# Sheet1.net
KiCad netlist of a schematic drawn in Altium Designer
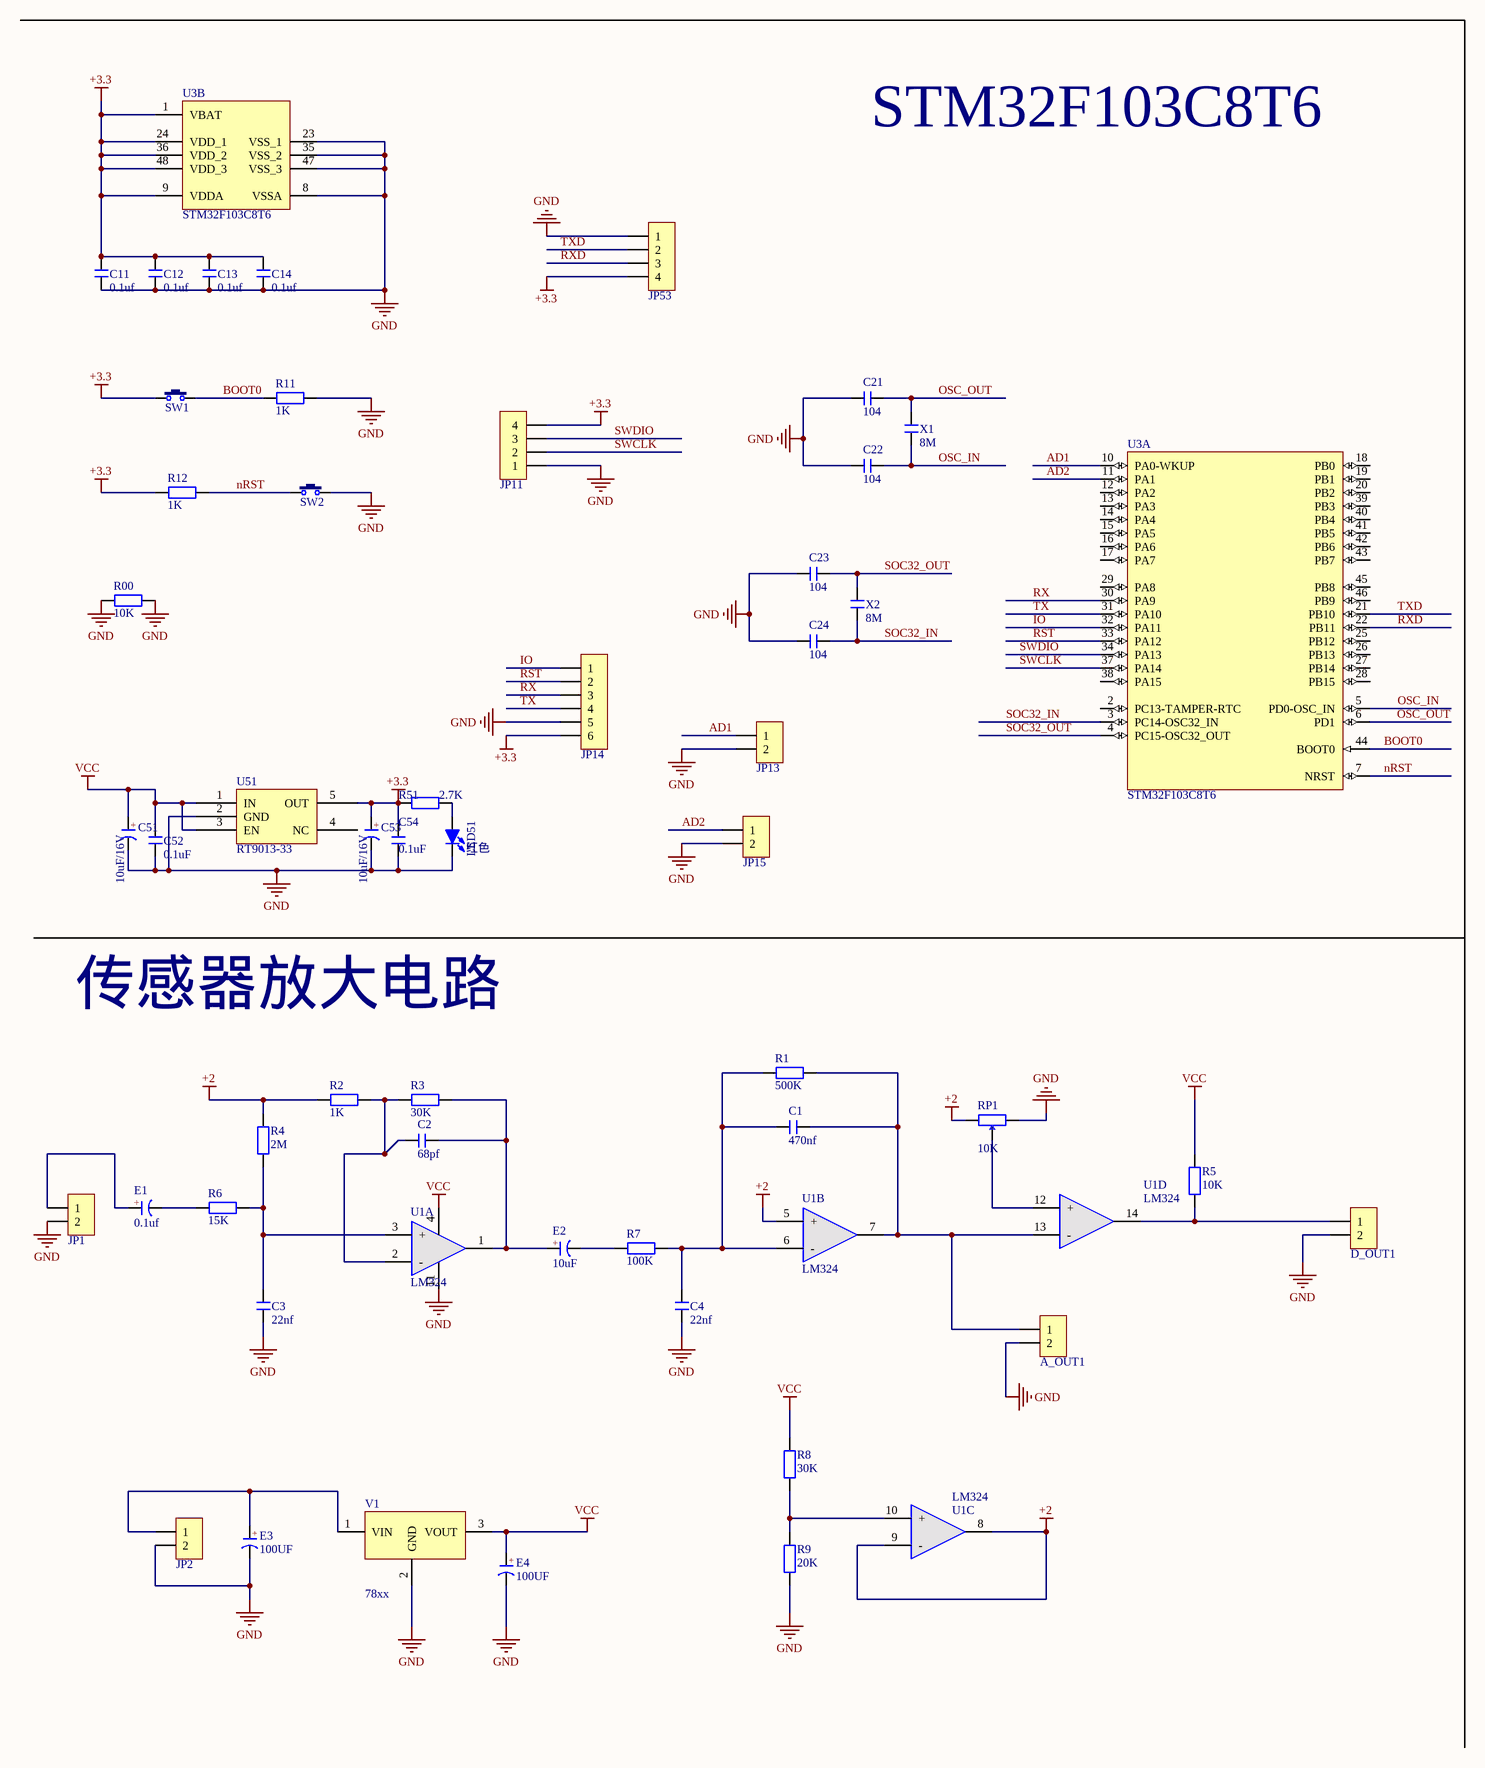
[diagram p0: Sheet1.SchDoc]

(export (version "E")
  (design (tool "Eeschema 10.0.6"))
  (components
    (comp (ref "A_OUT1")
      (value "HDR-1X2")
      (footprint "XH2.54-WI-2P")
      (description "2P接插件")
      (fields (field (name "版权归属") "封装库来自淘宝 ID：黄晶宝石"))
      (libsource (lib "5.3 - 接插件-脚距2.54 (100mil) ") (part "Header 2"))
    )
    (comp (ref "C1")
      (value "470nf")
      (footprint "C 0805_L")
      (description "贴片电容")
      (libsource (lib "0.1 - 电阻-电容-电感") (part "C"))
    )
    (comp (ref "C2")
      (value "68pf")
      (footprint "C 0805_L")
      (description "贴片电容")
      (libsource (lib "0.1 - 电阻-电容-电感") (part "C"))
    )
    (comp (ref "C3")
      (value "22nf")
      (footprint "C 0805_L")
      (description "贴片电容")
      (libsource (lib "0.1 - 电阻-电容-电感") (part "C"))
    )
    (comp (ref "C4")
      (value "22nf")
      (footprint "C 0805_L")
      (description "贴片电容")
      (libsource (lib "0.1 - 电阻-电容-电感") (part "C"))
    )
    (comp (ref "C11")
      (value "0.1uf")
      (footprint "C 0805_L")
      (description "贴片电容")
      (libsource (lib "0.1 - 电阻-电容-电感") (part "C"))
    )
    (comp (ref "C12")
      (value "0.1uf")
      (footprint "C 0805_L")
      (description "贴片电容")
      (libsource (lib "0.1 - 电阻-电容-电感") (part "C"))
    )
    (comp (ref "C13")
      (value "0.1uf")
      (footprint "C 0805_L")
      (description "贴片电容")
      (libsource (lib "0.1 - 电阻-电容-电感") (part "C"))
    )
    (comp (ref "C14")
      (value "0.1uf")
      (footprint "C 0805_L")
      (description "贴片电容")
      (libsource (lib "0.1 - 电阻-电容-电感") (part "C"))
    )
    (comp (ref "C21")
      (value "104")
      (footprint "C 0805_L")
      (description "贴片电容")
      (libsource (lib "0.1 - 电阻-电容-电感") (part "C"))
    )
    (comp (ref "C22")
      (value "104")
      (footprint "C 0805_L")
      (description "贴片电容")
      (libsource (lib "0.1 - 电阻-电容-电感") (part "C"))
    )
    (comp (ref "C23")
      (value "104")
      (footprint "C 0805_L")
      (description "贴片电容")
      (libsource (lib "0.1 - 电阻-电容-电感") (part "C"))
    )
    (comp (ref "C24")
      (value "104")
      (footprint "C 0805_L")
      (description "贴片电容")
      (libsource (lib "0.1 - 电阻-电容-电感") (part "C"))
    )
    (comp (ref "C51")
      (value "10uF/16V")
      (footprint "CD A(3216)")
      (description "贴片钽电容")
      (libsource (lib "TC264") (part "CT"))
    )
    (comp (ref "C52")
      (value "0.1uF")
      (footprint "C 0805_L")
      (description "贴片电容")
      (libsource (lib "TC264") (part "C"))
    )
    (comp (ref "C53")
      (value "10uF/16V")
      (footprint "CD A(3216)")
      (description "贴片钽电容")
      (libsource (lib "TC264") (part "CT"))
    )
    (comp (ref "C54")
      (value "0.1uF")
      (footprint "C 0805_L")
      (description "贴片电容")
      (libsource (lib "TC264") (part "C"))
    )
    (comp (ref "D_OUT1")
      (value "HDR-1X2")
      (footprint "XH2.54-WI-2P")
      (description "2P接插件")
      (fields (field (name "版权归属") "封装库来自淘宝 ID：黄晶宝石"))
      (libsource (lib "5.3 - 接插件-脚距2.54 (100mil) ") (part "Header 2"))
    )
    (comp (ref "E1")
      (value "0.1uf")
      (footprint "CM B(4*5.4)")
      (description "贴片电解电容")
      (fields (field (name "版权归属") "封装库来自淘宝 ID：黄晶宝石"))
      (libsource (lib "") (part "CE_SMD_1"))
    )
    (comp (ref "E2")
      (value "10uF")
      (footprint "CM B(4*5.4)")
      (description "贴片电解电容")
      (fields (field (name "版权归属") "封装库来自淘宝 ID：黄晶宝石"))
      (libsource (lib "") (part "CE_SMD_1"))
    )
    (comp (ref "E3")
      (value "100UF")
      (footprint "CM B(4*5.4)")
      (description "贴片电解电容")
      (fields (field (name "版权归属") "封装库来自淘宝 ID：黄晶宝石"))
      (libsource (lib "0.1 - 电阻-电容-电感") (part "CE_SMD"))
    )
    (comp (ref "E4")
      (value "100UF")
      (footprint "CM B(4*5.4)")
      (description "贴片电解电容")
      (fields (field (name "版权归属") "封装库来自淘宝 ID：黄晶宝石"))
      (libsource (lib "0.1 - 电阻-电容-电感") (part "CE_SMD"))
    )
    (comp (ref "JP1")
      (value "HDR-1X2")
      (footprint "XH2.54-WI-2P")
      (description "2P接插件")
      (fields (field (name "版权归属") "封装库来自淘宝 ID：黄晶宝石"))
      (libsource (lib "5.3 - 接插件-脚距2.54 (100mil) ") (part "Header 2"))
    )
    (comp (ref "JP2")
      (value "HDR-1X2")
      (footprint "XH2.54-WI-2P")
      (description "2P接插件")
      (fields (field (name "版权归属") "封装库来自淘宝 ID：黄晶宝石"))
      (libsource (lib "5.3 - 接插件-脚距2.54 (100mil) ") (part "Header 2"))
    )
    (comp (ref "JP11")
      (value "HDR-1X4")
      (footprint "XH2.54-WI-4P")
      (description "4P接插件")
      (fields (field (name "版权归属") "封装库来自淘宝 ID：黄晶宝石"))
      (libsource (lib "") (part "Header 4_1"))
    )
    (comp (ref "JP13")
      (value "HDR-1X2")
      (footprint "HDR2.54-LI-2P")
      (description "2P接插件")
      (fields (field (name "版权归属") "封装库来自淘宝 ID：黄晶宝石"))
      (libsource (lib "5.3 - 接插件-脚距2.54 (100mil) ") (part "Header 2"))
    )
    (comp (ref "JP14")
      (value "HDR-1X6")
      (footprint "HDR2.54-M-LI-6P")
      (description "6P接插件")
      (fields (field (name "版权归属") "封装库来自淘宝 ID：黄晶宝石"))
      (libsource (lib "5.3 - 接插件-脚距2.54 (100mil) ") (part "Header 6"))
    )
    (comp (ref "JP15")
      (value "HDR-1X2")
      (footprint "HDR2.54-LI-2P")
      (description "2P接插件")
      (fields (field (name "版权归属") "封装库来自淘宝 ID：黄晶宝石"))
      (libsource (lib "5.3 - 接插件-脚距2.54 (100mil) ") (part "Header 2"))
    )
    (comp (ref "JP53")
      (value "HDR-1X4")
      (footprint "HDR2.54-M-LI-4P")
      (description "4P接插件")
      (fields (field (name "版权归属") "封装库来自淘宝 ID：黄晶宝石"))
      (libsource (lib "5.3 - 接插件-脚距2.54 (100mil) ") (part "Header 4"))
    )
    (comp (ref "LED51")
      (value "红色")
      (footprint "LED 0805G")
      (description "贴片LED")
      (fields (field (name "版权归属") "封装库来自淘宝 ID：黄晶宝石"))
      (libsource (lib "TC264") (part "LED-SMD"))
    )
    (comp (ref "R00")
      (value "10K")
      (footprint "R 0805_L")
      (description "贴片电阻")
      (fields (field (name "版权归属") "来自淘宝 ID：黄晶宝石"))
      (libsource (lib "0.1 - 电阻-电容-电感") (part "R"))
    )
    (comp (ref "R1")
      (value "500K")
      (footprint "R 0805_L")
      (description "贴片电阻")
      (fields (field (name "版权归属") "来自淘宝 ID：黄晶宝石"))
      (libsource (lib "0.1 - 电阻-电容-电感") (part "R"))
    )
    (comp (ref "R2")
      (value "1K")
      (footprint "R 0805_L")
      (description "贴片电阻")
      (fields (field (name "版权归属") "来自淘宝 ID：黄晶宝石"))
      (libsource (lib "0.1 - 电阻-电容-电感") (part "R"))
    )
    (comp (ref "R3")
      (value "30K")
      (footprint "R 0805_L")
      (description "贴片电阻")
      (fields (field (name "版权归属") "来自淘宝 ID：黄晶宝石"))
      (libsource (lib "0.1 - 电阻-电容-电感") (part "R"))
    )
    (comp (ref "R4")
      (value "2M")
      (footprint "R 0805_L")
      (description "贴片电阻")
      (fields (field (name "版权归属") "来自淘宝 ID：黄晶宝石"))
      (libsource (lib "0.1 - 电阻-电容-电感") (part "R"))
    )
    (comp (ref "R5")
      (value "10K")
      (footprint "R 0805_L")
      (description "贴片电阻")
      (fields (field (name "版权归属") "来自淘宝 ID：黄晶宝石"))
      (libsource (lib "0.1 - 电阻-电容-电感") (part "R"))
    )
    (comp (ref "R6")
      (value "15K")
      (footprint "R 0805_L")
      (description "贴片电阻")
      (fields (field (name "版权归属") "来自淘宝 ID：黄晶宝石"))
      (libsource (lib "0.1 - 电阻-电容-电感") (part "R"))
    )
    (comp (ref "R7")
      (value "100K")
      (footprint "R 0805_L")
      (description "贴片电阻")
      (fields (field (name "版权归属") "来自淘宝 ID：黄晶宝石"))
      (libsource (lib "0.1 - 电阻-电容-电感") (part "R"))
    )
    (comp (ref "R8")
      (value "30K")
      (footprint "R 0805_L")
      (description "贴片电阻")
      (fields (field (name "版权归属") "来自淘宝 ID：黄晶宝石"))
      (libsource (lib "0.1 - 电阻-电容-电感") (part "R"))
    )
    (comp (ref "R9")
      (value "20K")
      (footprint "R 0805_L")
      (description "贴片电阻")
      (fields (field (name "版权归属") "来自淘宝 ID：黄晶宝石"))
      (libsource (lib "0.1 - 电阻-电容-电感") (part "R"))
    )
    (comp (ref "R11")
      (value "1K")
      (footprint "R 0805_L")
      (description "贴片电阻")
      (fields (field (name "版权归属") "来自淘宝 ID：黄晶宝石"))
      (libsource (lib "0.1 - 电阻-电容-电感") (part "R"))
    )
    (comp (ref "R12")
      (value "1K")
      (footprint "R 0805_L")
      (description "贴片电阻")
      (fields (field (name "版权归属") "来自淘宝 ID：黄晶宝石"))
      (libsource (lib "0.1 - 电阻-电容-电感") (part "R"))
    )
    (comp (ref "R51")
      (value "2.7K")
      (footprint "R 0805_L")
      (description "贴片电阻")
      (fields (field (name "版权归属") "来自淘宝 ID：黄晶宝石"))
      (libsource (lib "TC264") (part "R"))
    )
    (comp (ref "RP1")
      (value "10K")
      (footprint "3296W")
      (description "单联电位器")
      (fields (field (name "版权归属") "封装库来自淘宝 ID：黄晶宝石"))
      (libsource (lib "0.1 - 电阻-电容-电感") (part "RP"))
    )
    (comp (ref "SW1")
      (value "3x6x5")
      (footprint "TSW SMD-3*6*2.5")
      (description "3x6轻触开关")
      (fields (field (name "版权归属") "封装库来自淘宝 ID：黄晶宝石"))
      (libsource (lib "0.7 - 常用按键-开关") (part "TSW 3x6"))
    )
    (comp (ref "SW2")
      (value "3x6x5")
      (footprint "TSW SMD-3*6*2.5")
      (description "3x6轻触开关")
      (fields (field (name "版权归属") "封装库来自淘宝 ID：黄晶宝石"))
      (libsource (lib "0.7 - 常用按键-开关") (part "TSW 3x6"))
    )
    (comp (ref "U1")
      (value "LM324")
      (footprint "SOP14_M")
      (description "4运放")
      (libsource (lib "1.0 - 常见芯片") (part "LM324"))
    )
    (comp (ref "U3")
      (value "STM32F103C8T6")
      (footprint "LQFP48_N")
      (libsource (lib "2.3 - STM32 F1系列MCU 集成库") (part "STM32F103C8T6"))
    )
    (comp (ref "U51")
      (value "RT9013-33")
      (footprint "SOT23-5")
      (description "稳压芯片")
      (libsource (lib "TC264") (part "RT9013-33"))
    )
    (comp (ref "V1")
      (value "78xx")
      (footprint "TO252")
      (description "线性稳压芯片")
      (libsource (lib "1.1 - 电源类芯片") (part "78xx"))
    )
    (comp (ref "X1")
      (value "8M")
      (footprint "C 1206_M")
      (description "贴片电容")
      (libsource (lib "0.1 - 电阻-电容-电感") (part "C"))
    )
    (comp (ref "X2")
      (value "8M")
      (footprint "C 1206_M")
      (description "贴片电容")
      (libsource (lib "0.1 - 电阻-电容-电感") (part "C"))
    )
  )
  (nets
    (net (code "1") (name "+2") (class "Default")
      (node (ref "R2") (pin "1") (pinfunction "1_1") (pintype "passive"))
      (node (ref "R4") (pin "2") (pinfunction "2_2") (pintype "passive"))
      (node (ref "RP1") (pin "3") (pinfunction "3_3") (pintype "passive"))
      (node (ref "U1") (pin "5") (pinfunction "+_5") (pintype "passive"))
      (node (ref "U1") (pin "8") (pinfunction "OUT_8") (pintype "passive"))
      (node (ref "U1") (pin "9") (pinfunction "-_9") (pintype "passive"))
    )
    (net (code "2") (name "+3.3") (class "Default")
      (node (ref "C11") (pin "2") (pinfunction "2_2") (pintype "passive"))
      (node (ref "C12") (pin "2") (pinfunction "2_2") (pintype "passive"))
      (node (ref "C13") (pin "2") (pinfunction "2_2") (pintype "passive"))
      (node (ref "C14") (pin "2") (pinfunction "2_2") (pintype "passive"))
      (node (ref "C53") (pin "1") (pinfunction "A_1") (pintype "passive"))
      (node (ref "C54") (pin "2") (pinfunction "2_2") (pintype "passive"))
      (node (ref "JP11") (pin "4") (pinfunction "4_4") (pintype "passive"))
      (node (ref "JP14") (pin "6") (pinfunction "6_6") (pintype "passive"))
      (node (ref "JP53") (pin "4") (pinfunction "4_4") (pintype "passive"))
      (node (ref "R12") (pin "1") (pinfunction "1_1") (pintype "passive"))
      (node (ref "R51") (pin "1") (pinfunction "1_1") (pintype "passive"))
      (node (ref "SW1") (pin "1") (pinfunction "1_1") (pintype "passive"))
      (node (ref "U3") (pin "1") (pinfunction "VBAT_1") (pintype "power_in"))
      (node (ref "U3") (pin "24") (pinfunction "VDD_1_24") (pintype "power_in"))
      (node (ref "U3") (pin "36") (pinfunction "VDD_2_36") (pintype "power_in"))
      (node (ref "U3") (pin "48") (pinfunction "VDD_3_48") (pintype "power_in"))
      (node (ref "U3") (pin "9") (pinfunction "VDDA_9") (pintype "power_in"))
      (node (ref "U51") (pin "5") (pinfunction "OUT_5") (pintype "passive"))
    )
    (net (code "3") (name "/AD1") (class "Default")
      (node (ref "JP13") (pin "1") (pinfunction "1_1") (pintype "passive"))
      (node (ref "U3") (pin "10") (pinfunction "PA0-WKUP_10") (pintype "bidirectional"))
    )
    (net (code "4") (name "/AD2") (class "Default")
      (node (ref "JP15") (pin "1") (pinfunction "1_1") (pintype "passive"))
      (node (ref "U3") (pin "11") (pinfunction "PA1_11") (pintype "bidirectional"))
    )
    (net (code "5") (name "/BOOT0") (class "Default")
      (node (ref "R11") (pin "1") (pinfunction "1_1") (pintype "passive"))
      (node (ref "SW1") (pin "2") (pinfunction "2_2") (pintype "passive"))
      (node (ref "U3") (pin "44") (pinfunction "BOOT0_44") (pintype "input"))
    )
    (net (code "6") (name "/IO") (class "Default")
      (node (ref "JP14") (pin "1") (pinfunction "1_1") (pintype "passive"))
      (node (ref "U3") (pin "32") (pinfunction "PA11_32") (pintype "bidirectional"))
    )
    (net (code "7") (name "/OSC_IN") (class "Default")
      (node (ref "C22") (pin "2") (pinfunction "2_2") (pintype "passive"))
      (node (ref "U3") (pin "5") (pinfunction "PD0-OSC_IN_5") (pintype "bidirectional"))
      (node (ref "X1") (pin "1") (pinfunction "1_1") (pintype "passive"))
    )
    (net (code "8") (name "/OSC_OUT") (class "Default")
      (node (ref "C21") (pin "2") (pinfunction "2_2") (pintype "passive"))
      (node (ref "U3") (pin "6") (pinfunction "PD1_6") (pintype "bidirectional"))
      (node (ref "X1") (pin "2") (pinfunction "2_2") (pintype "passive"))
    )
    (net (code "9") (name "/RST") (class "Default")
      (node (ref "JP14") (pin "2") (pinfunction "2_2") (pintype "passive"))
      (node (ref "U3") (pin "33") (pinfunction "PA12_33") (pintype "bidirectional"))
    )
    (net (code "10") (name "/RX") (class "Default")
      (node (ref "JP14") (pin "3") (pinfunction "3_3") (pintype "passive"))
      (node (ref "U3") (pin "30") (pinfunction "PA9_30") (pintype "bidirectional"))
    )
    (net (code "11") (name "/RXD") (class "Default")
      (node (ref "JP53") (pin "3") (pinfunction "3_3") (pintype "passive"))
      (node (ref "U3") (pin "22") (pinfunction "PB11_22") (pintype "bidirectional"))
    )
    (net (code "12") (name "/SOC32_IN") (class "Default")
      (node (ref "C24") (pin "2") (pinfunction "2_2") (pintype "passive"))
      (node (ref "U3") (pin "3") (pinfunction "PC14-OSC32_IN_3") (pintype "bidirectional"))
      (node (ref "X2") (pin "1") (pinfunction "1_1") (pintype "passive"))
    )
    (net (code "13") (name "/SOC32_OUT") (class "Default")
      (node (ref "C23") (pin "2") (pinfunction "2_2") (pintype "passive"))
      (node (ref "U3") (pin "4") (pinfunction "PC15-OSC32_OUT_4") (pintype "bidirectional"))
      (node (ref "X2") (pin "2") (pinfunction "2_2") (pintype "passive"))
    )
    (net (code "14") (name "/SWCLK") (class "Default")
      (node (ref "JP11") (pin "2") (pinfunction "2_2") (pintype "passive"))
      (node (ref "U3") (pin "37") (pinfunction "PA14_37") (pintype "bidirectional"))
    )
    (net (code "15") (name "/SWDIO") (class "Default")
      (node (ref "JP11") (pin "3") (pinfunction "3_3") (pintype "passive"))
      (node (ref "U3") (pin "34") (pinfunction "PA13_34") (pintype "bidirectional"))
    )
    (net (code "16") (name "/TX") (class "Default")
      (node (ref "JP14") (pin "4") (pinfunction "4_4") (pintype "passive"))
      (node (ref "U3") (pin "31") (pinfunction "PA10_31") (pintype "bidirectional"))
    )
    (net (code "17") (name "/TXD") (class "Default")
      (node (ref "JP53") (pin "2") (pinfunction "2_2") (pintype "passive"))
      (node (ref "U3") (pin "21") (pinfunction "PB10_21") (pintype "bidirectional"))
    )
    (net (code "18") (name "/nRST") (class "Default")
      (node (ref "R12") (pin "2") (pinfunction "2_2") (pintype "passive"))
      (node (ref "SW2") (pin "1") (pinfunction "1_1") (pintype "passive"))
      (node (ref "U3") (pin "7") (pinfunction "NRST_7") (pintype "bidirectional"))
    )
    (net (code "19") (name "GND") (class "Default")
      (node (ref "A_OUT1") (pin "2") (pinfunction "2_2") (pintype "passive"))
      (node (ref "C11") (pin "1") (pinfunction "1_1") (pintype "passive"))
      (node (ref "C12") (pin "1") (pinfunction "1_1") (pintype "passive"))
      (node (ref "C13") (pin "1") (pinfunction "1_1") (pintype "passive"))
      (node (ref "C14") (pin "1") (pinfunction "1_1") (pintype "passive"))
      (node (ref "C21") (pin "1") (pinfunction "1_1") (pintype "passive"))
      (node (ref "C22") (pin "1") (pinfunction "1_1") (pintype "passive"))
      (node (ref "C23") (pin "1") (pinfunction "1_1") (pintype "passive"))
      (node (ref "C24") (pin "1") (pinfunction "1_1") (pintype "passive"))
      (node (ref "C3") (pin "1") (pinfunction "1_1") (pintype "passive"))
      (node (ref "C4") (pin "1") (pinfunction "1_1") (pintype "passive"))
      (node (ref "C51") (pin "2") (pinfunction "K_2") (pintype "passive"))
      (node (ref "C52") (pin "1") (pinfunction "1_1") (pintype "passive"))
      (node (ref "C53") (pin "2") (pinfunction "K_2") (pintype "passive"))
      (node (ref "C54") (pin "1") (pinfunction "1_1") (pintype "passive"))
      (node (ref "D_OUT1") (pin "2") (pinfunction "2_2") (pintype "passive"))
      (node (ref "E3") (pin "2") (pinfunction "K_2") (pintype "passive"))
      (node (ref "E4") (pin "2") (pinfunction "K_2") (pintype "passive"))
      (node (ref "JP1") (pin "2") (pinfunction "2_2") (pintype "passive"))
      (node (ref "JP11") (pin "1") (pinfunction "1_1") (pintype "passive"))
      (node (ref "JP13") (pin "2") (pinfunction "2_2") (pintype "passive"))
      (node (ref "JP14") (pin "5") (pinfunction "5_5") (pintype "passive"))
      (node (ref "JP15") (pin "2") (pinfunction "2_2") (pintype "passive"))
      (node (ref "JP2") (pin "2") (pinfunction "2_2") (pintype "passive"))
      (node (ref "JP53") (pin "1") (pinfunction "1_1") (pintype "passive"))
      (node (ref "LED51") (pin "2") (pinfunction "K_2") (pintype "passive"))
      (node (ref "R00") (pin "1") (pinfunction "1_1") (pintype "passive"))
      (node (ref "R00") (pin "2") (pinfunction "2_2") (pintype "passive"))
      (node (ref "R11") (pin "2") (pinfunction "2_2") (pintype "passive"))
      (node (ref "R9") (pin "1") (pinfunction "1_1") (pintype "passive"))
      (node (ref "RP1") (pin "1") (pinfunction "1_1") (pintype "passive"))
      (node (ref "SW2") (pin "2") (pinfunction "2_2") (pintype "passive"))
      (node (ref "U1") (pin "11") (pinfunction "V-_11") (pintype "passive"))
      (node (ref "U3") (pin "23") (pinfunction "VSS_1_23") (pintype "power_in"))
      (node (ref "U3") (pin "35") (pinfunction "VSS_2_35") (pintype "power_in"))
      (node (ref "U3") (pin "47") (pinfunction "VSS_3_47") (pintype "power_in"))
      (node (ref "U3") (pin "8") (pinfunction "VSSA_8") (pintype "power_in"))
      (node (ref "U51") (pin "2") (pinfunction "GND_2") (pintype "passive"))
      (node (ref "V1") (pin "2") (pinfunction "GND_2") (pintype "passive"))
    )
    (net (code "20") (name "Net-(E1-A)") (class "Default")
      (node (ref "E1") (pin "1") (pinfunction "A_1") (pintype "passive"))
      (node (ref "JP1") (pin "1") (pinfunction "1_1") (pintype "passive"))
    )
    (net (code "21") (name "Net-(E1-K)") (class "Default")
      (node (ref "E1") (pin "2") (pinfunction "K_2") (pintype "passive"))
      (node (ref "R6") (pin "1") (pinfunction "1_1") (pintype "passive"))
    )
    (net (code "22") (name "Net-(E2-A)") (class "Default")
      (node (ref "C2") (pin "2") (pinfunction "2_2") (pintype "passive"))
      (node (ref "E2") (pin "1") (pinfunction "A_1") (pintype "passive"))
      (node (ref "R3") (pin "2") (pinfunction "2_2") (pintype "passive"))
      (node (ref "U1") (pin "1") (pinfunction "OUT_1") (pintype "passive"))
    )
    (net (code "23") (name "Net-(E2-K)") (class "Default")
      (node (ref "E2") (pin "2") (pinfunction "K_2") (pintype "passive"))
      (node (ref "R7") (pin "1") (pinfunction "1_1") (pintype "passive"))
    )
    (net (code "24") (name "Net-(E3-A)") (class "Default")
      (node (ref "E3") (pin "1") (pinfunction "A_1") (pintype "passive"))
      (node (ref "JP2") (pin "1") (pinfunction "1_1") (pintype "passive"))
      (node (ref "V1") (pin "1") (pinfunction "VIN_1") (pintype "passive"))
    )
    (net (code "25") (name "Net-(LED51-A)") (class "Default")
      (node (ref "LED51") (pin "1") (pinfunction "A_1") (pintype "passive"))
      (node (ref "R51") (pin "2") (pinfunction "2_2") (pintype "passive"))
    )
    (net (code "26") (name "Net-(U1A-+)") (class "Default")
      (node (ref "C3") (pin "2") (pinfunction "2_2") (pintype "passive"))
      (node (ref "R4") (pin "1") (pinfunction "1_1") (pintype "passive"))
      (node (ref "R6") (pin "2") (pinfunction "2_2") (pintype "passive"))
      (node (ref "U1") (pin "3") (pinfunction "+_3") (pintype "passive"))
    )
    (net (code "27") (name "Net-(U1A--)") (class "Default")
      (node (ref "C2") (pin "1") (pinfunction "1_1") (pintype "passive"))
      (node (ref "R2") (pin "2") (pinfunction "2_2") (pintype "passive"))
      (node (ref "R3") (pin "1") (pinfunction "1_1") (pintype "passive"))
      (node (ref "U1") (pin "2") (pinfunction "-_2") (pintype "passive"))
    )
    (net (code "28") (name "Net-(U1B--)") (class "Default")
      (node (ref "C1") (pin "1") (pinfunction "1_1") (pintype "passive"))
      (node (ref "C4") (pin "2") (pinfunction "2_2") (pintype "passive"))
      (node (ref "R1") (pin "1") (pinfunction "1_1") (pintype "passive"))
      (node (ref "R7") (pin "2") (pinfunction "2_2") (pintype "passive"))
      (node (ref "U1") (pin "6") (pinfunction "-_6") (pintype "passive"))
    )
    (net (code "29") (name "Net-(U1B-OUT)") (class "Default")
      (node (ref "A_OUT1") (pin "1") (pinfunction "1_1") (pintype "passive"))
      (node (ref "C1") (pin "2") (pinfunction "2_2") (pintype "passive"))
      (node (ref "R1") (pin "2") (pinfunction "2_2") (pintype "passive"))
      (node (ref "U1") (pin "13") (pinfunction "-_13") (pintype "passive"))
      (node (ref "U1") (pin "7") (pinfunction "OUT_7") (pintype "passive"))
    )
    (net (code "30") (name "Net-(U1C-+)") (class "Default")
      (node (ref "R8") (pin "1") (pinfunction "1_1") (pintype "passive"))
      (node (ref "R9") (pin "2") (pinfunction "2_2") (pintype "passive"))
      (node (ref "U1") (pin "10") (pinfunction "+_10") (pintype "passive"))
    )
    (net (code "31") (name "Net-(U1D-+)") (class "Default")
      (node (ref "RP1") (pin "2") (pinfunction "2_2") (pintype "passive"))
      (node (ref "U1") (pin "12") (pinfunction "+_12") (pintype "passive"))
    )
    (net (code "32") (name "Net-(U1D-OUT)") (class "Default")
      (node (ref "D_OUT1") (pin "1") (pinfunction "1_1") (pintype "passive"))
      (node (ref "R5") (pin "1") (pinfunction "1_1") (pintype "passive"))
      (node (ref "U1") (pin "14") (pinfunction "OUT_14") (pintype "passive"))
    )
    (net (code "33") (name "VCC") (class "Default")
      (node (ref "C51") (pin "1") (pinfunction "A_1") (pintype "passive"))
      (node (ref "C52") (pin "2") (pinfunction "2_2") (pintype "passive"))
      (node (ref "E4") (pin "1") (pinfunction "A_1") (pintype "passive"))
      (node (ref "R5") (pin "2") (pinfunction "2_2") (pintype "passive"))
      (node (ref "R8") (pin "2") (pinfunction "2_2") (pintype "passive"))
      (node (ref "U1") (pin "4") (pinfunction "V+_4") (pintype "passive"))
      (node (ref "U51") (pin "1") (pinfunction "IN_1") (pintype "passive"))
      (node (ref "U51") (pin "3") (pinfunction "EN_3") (pintype "passive"))
      (node (ref "V1") (pin "3") (pinfunction "VOUT_3") (pintype "passive"))
    )
    (net (code "34") (name "unconnected-(U3A-PA2-Pad12)") (class "Default")
      (node (ref "U3") (pin "12") (pinfunction "PA2_12") (pintype "bidirectional"))
    )
    (net (code "35") (name "unconnected-(U3A-PA3-Pad13)") (class "Default")
      (node (ref "U3") (pin "13") (pinfunction "PA3_13") (pintype "bidirectional"))
    )
    (net (code "36") (name "unconnected-(U3A-PA4-Pad14)") (class "Default")
      (node (ref "U3") (pin "14") (pinfunction "PA4_14") (pintype "bidirectional"))
    )
    (net (code "37") (name "unconnected-(U3A-PA5-Pad15)") (class "Default")
      (node (ref "U3") (pin "15") (pinfunction "PA5_15") (pintype "bidirectional"))
    )
    (net (code "38") (name "unconnected-(U3A-PA6-Pad16)") (class "Default")
      (node (ref "U3") (pin "16") (pinfunction "PA6_16") (pintype "bidirectional"))
    )
    (net (code "39") (name "unconnected-(U3A-PA7-Pad17)") (class "Default")
      (node (ref "U3") (pin "17") (pinfunction "PA7_17") (pintype "bidirectional"))
    )
    (net (code "40") (name "unconnected-(U3A-PA8-Pad29)") (class "Default")
      (node (ref "U3") (pin "29") (pinfunction "PA8_29") (pintype "bidirectional"))
    )
    (net (code "41") (name "unconnected-(U3A-PA15-Pad38)") (class "Default")
      (node (ref "U3") (pin "38") (pinfunction "PA15_38") (pintype "bidirectional"))
    )
    (net (code "42") (name "unconnected-(U3A-PB0-Pad18)") (class "Default")
      (node (ref "U3") (pin "18") (pinfunction "PB0_18") (pintype "bidirectional"))
    )
    (net (code "43") (name "unconnected-(U3A-PB1-Pad19)") (class "Default")
      (node (ref "U3") (pin "19") (pinfunction "PB1_19") (pintype "bidirectional"))
    )
    (net (code "44") (name "unconnected-(U3A-PB2-Pad20)") (class "Default")
      (node (ref "U3") (pin "20") (pinfunction "PB2_20") (pintype "bidirectional"))
    )
    (net (code "45") (name "unconnected-(U3A-PB3-Pad39)") (class "Default")
      (node (ref "U3") (pin "39") (pinfunction "PB3_39") (pintype "bidirectional"))
    )
    (net (code "46") (name "unconnected-(U3A-PB4-Pad40)") (class "Default")
      (node (ref "U3") (pin "40") (pinfunction "PB4_40") (pintype "bidirectional"))
    )
    (net (code "47") (name "unconnected-(U3A-PB5-Pad41)") (class "Default")
      (node (ref "U3") (pin "41") (pinfunction "PB5_41") (pintype "bidirectional"))
    )
    (net (code "48") (name "unconnected-(U3A-PB6-Pad42)") (class "Default")
      (node (ref "U3") (pin "42") (pinfunction "PB6_42") (pintype "bidirectional"))
    )
    (net (code "49") (name "unconnected-(U3A-PB7-Pad43)") (class "Default")
      (node (ref "U3") (pin "43") (pinfunction "PB7_43") (pintype "bidirectional"))
    )
    (net (code "50") (name "unconnected-(U3A-PB8-Pad45)") (class "Default")
      (node (ref "U3") (pin "45") (pinfunction "PB8_45") (pintype "bidirectional"))
    )
    (net (code "51") (name "unconnected-(U3A-PB9-Pad46)") (class "Default")
      (node (ref "U3") (pin "46") (pinfunction "PB9_46") (pintype "bidirectional"))
    )
    (net (code "52") (name "unconnected-(U3A-PB12-Pad25)") (class "Default")
      (node (ref "U3") (pin "25") (pinfunction "PB12_25") (pintype "bidirectional"))
    )
    (net (code "53") (name "unconnected-(U3A-PB13-Pad26)") (class "Default")
      (node (ref "U3") (pin "26") (pinfunction "PB13_26") (pintype "bidirectional"))
    )
    (net (code "54") (name "unconnected-(U3A-PB14-Pad27)") (class "Default")
      (node (ref "U3") (pin "27") (pinfunction "PB14_27") (pintype "bidirectional"))
    )
    (net (code "55") (name "unconnected-(U3A-PB15-Pad28)") (class "Default")
      (node (ref "U3") (pin "28") (pinfunction "PB15_28") (pintype "bidirectional"))
    )
    (net (code "56") (name "unconnected-(U3A-PC13-TAMPER-RTC-Pad2)") (class "Default")
      (node (ref "U3") (pin "2") (pinfunction "PC13-TAMPER-RTC_2") (pintype "bidirectional"))
    )
    (net (code "57") (name "unconnected-(U51-NC-Pad4)") (class "Default")
      (node (ref "U51") (pin "4") (pinfunction "NC_4") (pintype "passive"))
    )
  )
)
